# Signal_Processing.net
KiCad netlist of a schematic drawn in Altium Designer
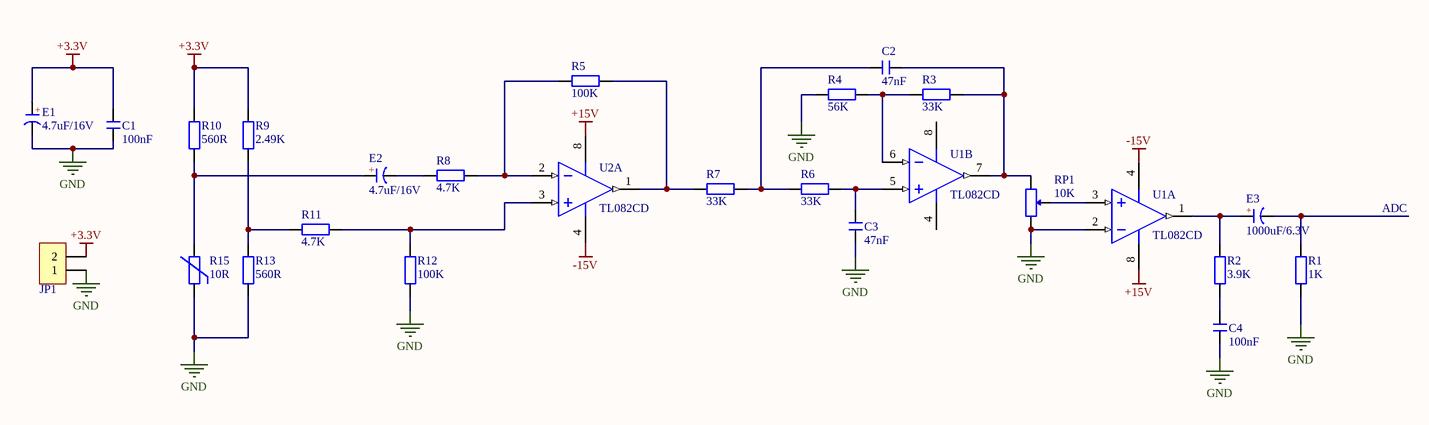
[diagram p0: Signal_Processing.SchDoc]

(export (version "E")
  (design (tool "Eeschema 10.0.6"))
  (components
    (comp (ref "C1")
      (value "100nF")
      (footprint "C 0603_L")
      (description "贴片电容")
      (libsource (lib "0.1 - 电阻-电容-电感") (part "C"))
    )
    (comp (ref "C2")
      (value "47nF")
      (footprint "C 0603_L")
      (description "贴片电容")
      (libsource (lib "0.1 - 电阻-电容-电感") (part "C"))
    )
    (comp (ref "C3")
      (value "47nF")
      (footprint "C 0603_L")
      (description "贴片电容")
      (libsource (lib "0.1 - 电阻-电容-电感") (part "C"))
    )
    (comp (ref "C4")
      (value "100nF")
      (footprint "C 0603_L")
      (description "贴片电容")
      (libsource (lib "0.1 - 电阻-电容-电感") (part "C"))
    )
    (comp (ref "E1")
      (value "4.7uF/16V")
      (footprint "CD A(3216)")
      (description "贴片钽电容")
      (libsource (lib "") (part "CT_1"))
    )
    (comp (ref "E2")
      (value "4.7uF/16V")
      (footprint "CD A(3216)")
      (description "贴片钽电容")
      (libsource (lib "0.1 - 电阻-电容-电感") (part "CT"))
    )
    (comp (ref "E3")
      (value "1000uF/6.3V")
      (footprint "CD E(7343H)")
      (description "贴片钽电容")
      (libsource (lib "0.1 - 电阻-电容-电感") (part "CT"))
    )
    (comp (ref "JP1")
      (value "HDR-1X2")
      (footprint "HDR2.54-LI-2P")
      (description "2P接插件")
      (fields (field (name "版权归属") "封装库来自淘宝 ID：黄晶宝石"))
      (libsource (lib "5.4 - 接插件-脚距2.54 (100mil) ") (part "Header 2"))
    )
    (comp (ref "R1")
      (value "1K")
      (footprint "R 0603_L")
      (description "贴片电阻")
      (fields (field (name "版权归属") "来自淘宝 ID：黄晶宝石"))
      (libsource (lib "0.1 - 电阻-电容-电感") (part "R"))
    )
    (comp (ref "R2")
      (value "3.9K")
      (footprint "R 0603_L")
      (description "贴片电阻")
      (fields (field (name "版权归属") "来自淘宝 ID：黄晶宝石"))
      (libsource (lib "0.1 - 电阻-电容-电感") (part "R"))
    )
    (comp (ref "R3")
      (value "33K")
      (footprint "R 0603_L")
      (description "贴片电阻")
      (fields (field (name "版权归属") "来自淘宝 ID：黄晶宝石"))
      (libsource (lib "0.1 - 电阻-电容-电感") (part "R"))
    )
    (comp (ref "R4")
      (value "56K")
      (footprint "R 0603_L")
      (description "贴片电阻")
      (fields (field (name "版权归属") "来自淘宝 ID：黄晶宝石"))
      (libsource (lib "0.1 - 电阻-电容-电感") (part "R"))
    )
    (comp (ref "R5")
      (value "100K")
      (footprint "R 0603_L")
      (description "贴片电阻")
      (fields (field (name "版权归属") "来自淘宝 ID：黄晶宝石"))
      (libsource (lib "0.1 - 电阻-电容-电感") (part "R"))
    )
    (comp (ref "R6")
      (value "33K")
      (footprint "R 0603_L")
      (description "贴片电阻")
      (fields (field (name "版权归属") "来自淘宝 ID：黄晶宝石"))
      (libsource (lib "0.1 - 电阻-电容-电感") (part "R"))
    )
    (comp (ref "R7")
      (value "33K")
      (footprint "R 0603_L")
      (description "贴片电阻")
      (fields (field (name "版权归属") "来自淘宝 ID：黄晶宝石"))
      (libsource (lib "0.1 - 电阻-电容-电感") (part "R"))
    )
    (comp (ref "R8")
      (value "4.7K")
      (footprint "R 0603_L")
      (description "贴片电阻")
      (fields (field (name "版权归属") "来自淘宝 ID：黄晶宝石"))
      (libsource (lib "0.1 - 电阻-电容-电感") (part "R"))
    )
    (comp (ref "R9")
      (value "2.49K")
      (footprint "R 0603_L")
      (description "贴片电阻")
      (fields (field (name "版权归属") "来自淘宝 ID：黄晶宝石"))
      (libsource (lib "0.1 - 电阻-电容-电感") (part "R"))
    )
    (comp (ref "R10")
      (value "560R")
      (footprint "R 0603_L")
      (description "贴片电阻")
      (fields (field (name "版权归属") "来自淘宝 ID：黄晶宝石"))
      (libsource (lib "0.1 - 电阻-电容-电感") (part "R"))
    )
    (comp (ref "R11")
      (value "4.7K")
      (footprint "R 0603_L")
      (description "贴片电阻")
      (fields (field (name "版权归属") "来自淘宝 ID：黄晶宝石"))
      (libsource (lib "0.1 - 电阻-电容-电感") (part "R"))
    )
    (comp (ref "R12")
      (value "100K")
      (footprint "R 0603_L")
      (description "贴片电阻")
      (fields (field (name "版权归属") "来自淘宝 ID：黄晶宝石"))
      (libsource (lib "0.1 - 电阻-电容-电感") (part "R"))
    )
    (comp (ref "R13")
      (value "560R")
      (footprint "R 0603_L")
      (description "贴片电阻")
      (fields (field (name "版权归属") "来自淘宝 ID：黄晶宝石"))
      (libsource (lib "0.1 - 电阻-电容-电感") (part "R"))
    )
    (comp (ref "R15")
      (value "10R")
      (footprint "VDR 9D-4.5")
      (description "压敏电阻")
      (fields (field (name "版权归属") "封装库来自淘宝 ID：黄晶宝石"))
      (libsource (lib "0.1 - 电阻-电容-电感") (part "R_VSR"))
    )
    (comp (ref "RP1")
      (value "10K")
      (footprint "3296W")
      (description "单联电位器")
      (fields (field (name "版权归属") "封装库来自淘宝 ID：黄晶宝石"))
      (libsource (lib "0.1 - 电阻-电容-电感") (part "RP"))
    )
    (comp (ref "U1")
      (value "TL082CD")
      (footprint "TI-D8_N")
      (fields (field (name "MANUFACTURER") "Texas Instruments"))
      (libsource (lib "TI Amplifiers and Linear Operational Amplifier General Purpose") (part "TL082CD"))
    )
    (comp (ref "U2")
      (value "TL082CD")
      (footprint "TI-D8_N")
      (fields (field (name "MANUFACTURER") "Texas Instruments"))
      (libsource (lib "TI Amplifiers and Linear Operational Amplifier General Purpose") (part "TL082CD"))
    )
  )
  (nets
    (net (code "1") (name "+3.3V") (class "Default")
      (node (ref "C1") (pin "2") (pinfunction "2_2") (pintype "passive"))
      (node (ref "E1") (pin "1") (pinfunction "A_1") (pintype "passive"))
      (node (ref "JP1") (pin "2") (pinfunction "2_2") (pintype "passive"))
      (node (ref "R10") (pin "2") (pinfunction "2_2") (pintype "passive"))
      (node (ref "R9") (pin "1") (pinfunction "1_1") (pintype "passive"))
    )
    (net (code "2") (name "+15V") (class "Default")
      (node (ref "U1") (pin "8") (pinfunction "VCC+_8") (pintype "power_in"))
      (node (ref "U2") (pin "8") (pinfunction "VCC+_8") (pintype "power_in"))
    )
    (net (code "3") (name "-15V") (class "Default")
      (node (ref "U1") (pin "4") (pinfunction "VCC-_4") (pintype "power_in"))
      (node (ref "U2") (pin "4") (pinfunction "VCC-_4") (pintype "power_in"))
    )
    (net (code "4") (name "GND") (class "Default")
      (node (ref "C1") (pin "1") (pinfunction "1_1") (pintype "passive"))
      (node (ref "C3") (pin "1") (pinfunction "1_1") (pintype "passive"))
      (node (ref "C4") (pin "1") (pinfunction "1_1") (pintype "passive"))
      (node (ref "E1") (pin "2") (pinfunction "K_2") (pintype "passive"))
      (node (ref "JP1") (pin "1") (pinfunction "1_1") (pintype "passive"))
      (node (ref "R1") (pin "1") (pinfunction "1_1") (pintype "passive"))
      (node (ref "R12") (pin "1") (pinfunction "1_1") (pintype "passive"))
      (node (ref "R13") (pin "1") (pinfunction "1_1") (pintype "passive"))
      (node (ref "R15") (pin "1") (pinfunction "1_1") (pintype "passive"))
      (node (ref "R4") (pin "1") (pinfunction "1_1") (pintype "passive"))
      (node (ref "RP1") (pin "3") (pinfunction "3_3") (pintype "passive"))
      (node (ref "U1") (pin "2") (pinfunction "IN1-_2") (pintype "input"))
    )
    (net (code "5") (name "Net-(C2-Pad1)") (class "Default")
      (node (ref "C2") (pin "1") (pinfunction "1_1") (pintype "passive"))
      (node (ref "R6") (pin "1") (pinfunction "1_1") (pintype "passive"))
      (node (ref "R7") (pin "2") (pinfunction "2_2") (pintype "passive"))
    )
    (net (code "6") (name "Net-(C4-Pad2)") (class "Default")
      (node (ref "C4") (pin "2") (pinfunction "2_2") (pintype "passive"))
      (node (ref "R2") (pin "1") (pinfunction "1_1") (pintype "passive"))
    )
    (net (code "7") (name "Net-(E2-A)") (class "Default")
      (node (ref "E2") (pin "1") (pinfunction "A_1") (pintype "passive"))
      (node (ref "R10") (pin "1") (pinfunction "1_1") (pintype "passive"))
      (node (ref "R15") (pin "2") (pinfunction "2_2") (pintype "passive"))
    )
    (net (code "8") (name "Net-(E2-K)") (class "Default")
      (node (ref "E2") (pin "2") (pinfunction "K_2") (pintype "passive"))
      (node (ref "R8") (pin "1") (pinfunction "1_1") (pintype "passive"))
    )
    (net (code "9") (name "Net-(E3-A)") (class "Default")
      (node (ref "E3") (pin "1") (pinfunction "A_1") (pintype "passive"))
      (node (ref "R2") (pin "2") (pinfunction "2_2") (pintype "passive"))
      (node (ref "U1") (pin "1") (pinfunction "OUT1_1") (pintype "output"))
    )
    (net (code "10") (name "Net-(E3-K)") (class "Default")
      (node (ref "E3") (pin "2") (pinfunction "K_2") (pintype "passive"))
      (node (ref "R1") (pin "2") (pinfunction "2_2") (pintype "passive"))
    )
    (net (code "11") (name "Net-(R11-Pad1)") (class "Default")
      (node (ref "R11") (pin "1") (pinfunction "1_1") (pintype "passive"))
      (node (ref "R13") (pin "2") (pinfunction "2_2") (pintype "passive"))
      (node (ref "R9") (pin "2") (pinfunction "2_2") (pintype "passive"))
    )
    (net (code "12") (name "Net-(U1A-IN1+)") (class "Default")
      (node (ref "RP1") (pin "2") (pinfunction "2_2") (pintype "passive"))
      (node (ref "U1") (pin "3") (pinfunction "IN1+_3") (pintype "input"))
    )
    (net (code "13") (name "Net-(U1B-IN2+)") (class "Default")
      (node (ref "C3") (pin "2") (pinfunction "2_2") (pintype "passive"))
      (node (ref "R6") (pin "2") (pinfunction "2_2") (pintype "passive"))
      (node (ref "U1") (pin "5") (pinfunction "IN2+_5") (pintype "input"))
    )
    (net (code "14") (name "Net-(U1B-IN2-)") (class "Default")
      (node (ref "R3") (pin "1") (pinfunction "1_1") (pintype "passive"))
      (node (ref "R4") (pin "2") (pinfunction "2_2") (pintype "passive"))
      (node (ref "U1") (pin "6") (pinfunction "IN2-_6") (pintype "input"))
    )
    (net (code "15") (name "Net-(U1B-OUT2)") (class "Default")
      (node (ref "C2") (pin "2") (pinfunction "2_2") (pintype "passive"))
      (node (ref "R3") (pin "2") (pinfunction "2_2") (pintype "passive"))
      (node (ref "RP1") (pin "1") (pinfunction "1_1") (pintype "passive"))
      (node (ref "U1") (pin "7") (pinfunction "OUT2_7") (pintype "output"))
    )
    (net (code "16") (name "Net-(U2A-IN1+)") (class "Default")
      (node (ref "R11") (pin "2") (pinfunction "2_2") (pintype "passive"))
      (node (ref "R12") (pin "2") (pinfunction "2_2") (pintype "passive"))
      (node (ref "U2") (pin "3") (pinfunction "IN1+_3") (pintype "input"))
    )
    (net (code "17") (name "Net-(U2A-IN1-)") (class "Default")
      (node (ref "R5") (pin "1") (pinfunction "1_1") (pintype "passive"))
      (node (ref "R8") (pin "2") (pinfunction "2_2") (pintype "passive"))
      (node (ref "U2") (pin "2") (pinfunction "IN1-_2") (pintype "input"))
    )
    (net (code "18") (name "Net-(U2A-OUT1)") (class "Default")
      (node (ref "R5") (pin "2") (pinfunction "2_2") (pintype "passive"))
      (node (ref "R7") (pin "1") (pinfunction "1_1") (pintype "passive"))
      (node (ref "U2") (pin "1") (pinfunction "OUT1_1") (pintype "output"))
    )
    (net (code "19") (name "unconnected-(U1B-VCC+-Pad8)") (class "Default")
      (node (ref "U1") (pin "8") (pinfunction "VCC+_8") (pintype "power_in"))
    )
    (net (code "20") (name "unconnected-(U1B-VCC--Pad4)") (class "Default")
      (node (ref "U1") (pin "4") (pinfunction "VCC-_4") (pintype "power_in"))
    )
  )
)
